# BMP280_board.net
KiCad netlist of a schematic drawn in EAGLE
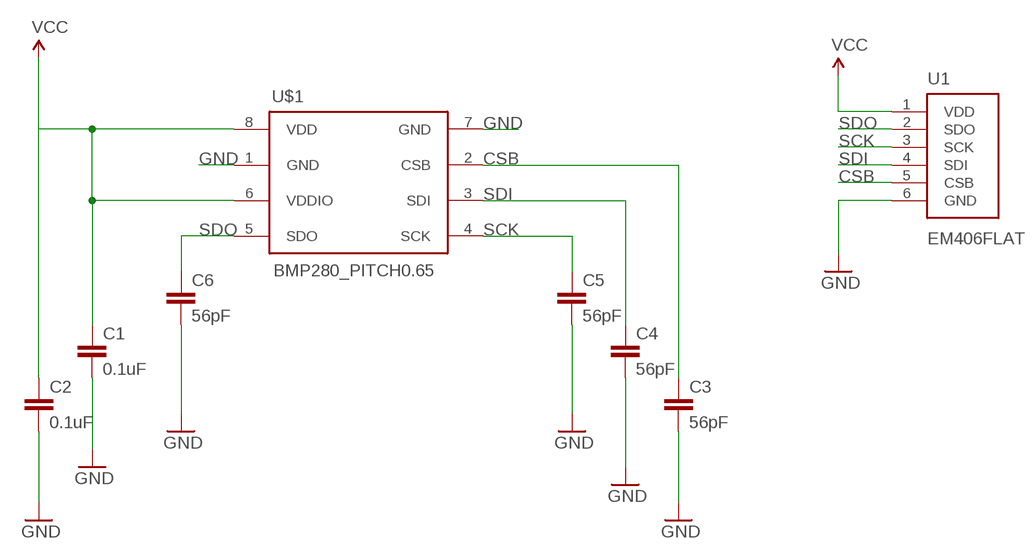
[diagram p0: schematic, sheet 1]

(export (version "E")
  (design (tool "Eeschema 10.0.6"))
  (components
    (comp (ref "C1")
      (value "0.1uF")
      (footprint "eagle-import:0603-CAP")
      (libsource (lib "eagle-import") (part "0.1UF-25V(+80/-20%)(0603)"))
    )
    (comp (ref "C2")
      (value "0.1uF")
      (footprint "eagle-import:0603-CAP")
      (libsource (lib "eagle-import") (part "0.1UF-25V(+80/-20%)(0603)"))
    )
    (comp (ref "C3")
      (value "56pF")
      (footprint "eagle-import:0603-CAP")
      (libsource (lib "eagle-import") (part "0.1UF-25V(+80/-20%)(0603)"))
    )
    (comp (ref "C4")
      (value "56pF")
      (footprint "eagle-import:0603-CAP")
      (libsource (lib "eagle-import") (part "0.1UF-25V(+80/-20%)(0603)"))
    )
    (comp (ref "C5")
      (value "56pF")
      (footprint "eagle-import:0603-CAP")
      (libsource (lib "eagle-import") (part "0.1UF-25V(+80/-20%)(0603)"))
    )
    (comp (ref "C6")
      (value "56pF")
      (footprint "eagle-import:0603-CAP")
      (libsource (lib "eagle-import") (part "0.1UF-25V(+80/-20%)(0603)"))
    )
    (comp (ref "U$1")
      (value "BMP280_PITCH0.65")
      (footprint "eagle-import:LGA-8")
      (libsource (lib "eagle-import") (part "BMP280_PITCH0.65"))
    )
    (comp (ref "U1")
      (value "EM406FLAT")
      (footprint "eagle-import:EM406-FLAT")
      (libsource (lib "eagle-import") (part "EM406FLAT"))
    )
  )
  (nets
    (net (code "1") (name "/CSB") (class "Default")
      (node (ref "C3") (pin "1") (pinfunction "1_1") (pintype "passive"))
      (node (ref "U$1") (pin "2") (pinfunction "CSB_2") (pintype "bidirectional"))
      (node (ref "U1") (pin "5") (pinfunction "CSB_5") (pintype "bidirectional"))
    )
    (net (code "2") (name "/SCK") (class "Default")
      (node (ref "C5") (pin "1") (pinfunction "1_1") (pintype "passive"))
      (node (ref "U$1") (pin "4") (pinfunction "SCK_4") (pintype "bidirectional"))
      (node (ref "U1") (pin "3") (pinfunction "SCK_3") (pintype "bidirectional"))
    )
    (net (code "3") (name "/SDI") (class "Default")
      (node (ref "C4") (pin "1") (pinfunction "1_1") (pintype "passive"))
      (node (ref "U$1") (pin "3") (pinfunction "SDI_3") (pintype "bidirectional"))
      (node (ref "U1") (pin "4") (pinfunction "SDI_4") (pintype "bidirectional"))
    )
    (net (code "4") (name "/SDO") (class "Default")
      (node (ref "C6") (pin "1") (pinfunction "1_1") (pintype "passive"))
      (node (ref "U$1") (pin "5") (pinfunction "SDO_5") (pintype "bidirectional"))
      (node (ref "U1") (pin "2") (pinfunction "SDO_2") (pintype "bidirectional"))
    )
    (net (code "5") (name "GND") (class "Default")
      (node (ref "C1") (pin "2") (pinfunction "2_2") (pintype "passive"))
      (node (ref "C2") (pin "2") (pinfunction "2_2") (pintype "passive"))
      (node (ref "C3") (pin "2") (pinfunction "2_2") (pintype "passive"))
      (node (ref "C4") (pin "2") (pinfunction "2_2") (pintype "passive"))
      (node (ref "C5") (pin "2") (pinfunction "2_2") (pintype "passive"))
      (node (ref "C6") (pin "2") (pinfunction "2_2") (pintype "passive"))
      (node (ref "U$1") (pin "1") (pinfunction "GND_1") (pintype "bidirectional"))
      (node (ref "U$1") (pin "7") (pinfunction "GND_7") (pintype "bidirectional"))
      (node (ref "U1") (pin "6") (pinfunction "GND_6") (pintype "bidirectional"))
    )
    (net (code "6") (name "VCC") (class "Default")
      (node (ref "C1") (pin "1") (pinfunction "1_1") (pintype "passive"))
      (node (ref "C2") (pin "1") (pinfunction "1_1") (pintype "passive"))
      (node (ref "U$1") (pin "6") (pinfunction "VDDIO_6") (pintype "bidirectional"))
      (node (ref "U$1") (pin "8") (pinfunction "VDD_8") (pintype "bidirectional"))
      (node (ref "U1") (pin "1") (pinfunction "VDD_1") (pintype "bidirectional"))
    )
  )
)
